# programm-adapter.net
KiCad netlist of a schematic drawn in EAGLE
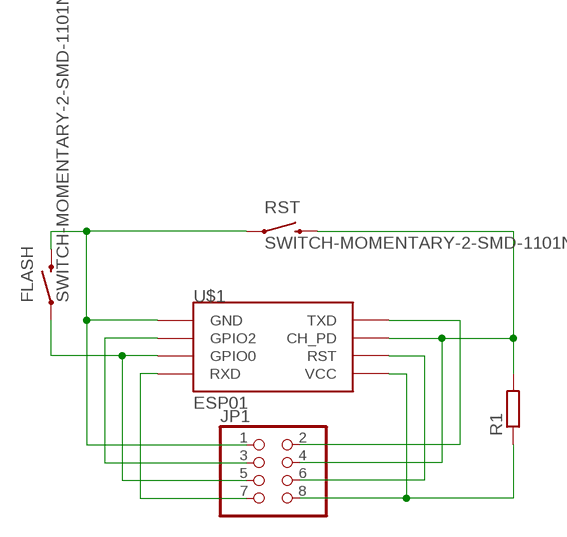
[diagram p0: schematic, sheet 1]

(export (version "E")
  (design (tool "Eeschema 10.0.6"))
  (components
    (comp (ref "FLASH")
      (value "SWITCH-MOMENTARY-2-SMD-1101NE")
      (footprint "eagle-import:TACTILE-SWITCH-1101NE")
      (libsource (lib "eagle-import") (part "SWITCH-MOMENTARY-2-SMD-1101NE"))
    )
    (comp (ref "JP1")
      (value "PINHD-2X4")
      (footprint "eagle-import:2X04")
      (libsource (lib "eagle-import") (part "PINHD-2X4"))
    )
    (comp (ref "R1")
      (value "R-EU_M0805")
      (footprint "eagle-import:M0805")
      (libsource (lib "eagle-import") (part "R-EU_M0805"))
    )
    (comp (ref "RST")
      (value "SWITCH-MOMENTARY-2-SMD-1101NE")
      (footprint "eagle-import:TACTILE-SWITCH-1101NE")
      (libsource (lib "eagle-import") (part "SWITCH-MOMENTARY-2-SMD-1101NE"))
    )
    (comp (ref "U$1")
      (value "ESP01")
      (footprint "eagle-import:ESP01")
      (libsource (lib "eagle-import") (part "ESP01"))
    )
  )
  (nets
    (net (code "1") (name "Net-(FLASH-Pad1)") (class "Default")
      (node (ref "FLASH") (pin "1") (pinfunction "1_1") (pintype "passive"))
      (node (ref "JP1") (pin "5") (pinfunction "5_5") (pintype "passive"))
      (node (ref "U$1") (pin "GPIO0") (pinfunction "GPIO0_GPIO0") (pintype "bidirectional"))
    )
    (net (code "2") (name "Net-(FLASH-Pad2)") (class "Default")
      (node (ref "FLASH") (pin "2") (pinfunction "2_2") (pintype "passive"))
      (node (ref "JP1") (pin "1") (pinfunction "1_1") (pintype "passive"))
      (node (ref "RST") (pin "1") (pinfunction "1_1") (pintype "passive"))
      (node (ref "U$1") (pin "GND") (pinfunction "GND_GND") (pintype "bidirectional"))
    )
    (net (code "3") (name "Net-(JP1-Pad3)") (class "Default")
      (node (ref "JP1") (pin "3") (pinfunction "3_3") (pintype "passive"))
      (node (ref "U$1") (pin "GPIO2") (pinfunction "GPIO2_GPIO2") (pintype "bidirectional"))
    )
    (net (code "4") (name "Net-(JP1-Pad4)") (class "Default")
      (node (ref "JP1") (pin "4") (pinfunction "4_4") (pintype "passive"))
      (node (ref "R1") (pin "2") (pinfunction "2_2") (pintype "passive"))
      (node (ref "RST") (pin "2") (pinfunction "2_2") (pintype "passive"))
      (node (ref "U$1") (pin "CH_PD") (pinfunction "CH_PD_CH_PD") (pintype "bidirectional"))
    )
    (net (code "5") (name "Net-(JP1-Pad6)") (class "Default")
      (node (ref "JP1") (pin "6") (pinfunction "6_6") (pintype "passive"))
      (node (ref "U$1") (pin "RST") (pinfunction "RST_RST") (pintype "bidirectional"))
    )
    (net (code "6") (name "Net-(JP1-Pad8)") (class "Default")
      (node (ref "JP1") (pin "8") (pinfunction "8_8") (pintype "passive"))
      (node (ref "R1") (pin "1") (pinfunction "1_1") (pintype "passive"))
      (node (ref "U$1") (pin "VCC") (pinfunction "VCC_VCC") (pintype "bidirectional"))
    )
    (net (code "7") (name "Net-(U$1-RXD)") (class "Default")
      (node (ref "JP1") (pin "7") (pinfunction "7_7") (pintype "passive"))
      (node (ref "U$1") (pin "RX") (pinfunction "RXD_RX") (pintype "bidirectional"))
    )
    (net (code "8") (name "Net-(U$1-TXD)") (class "Default")
      (node (ref "JP1") (pin "2") (pinfunction "2_2") (pintype "passive"))
      (node (ref "U$1") (pin "TX") (pinfunction "TXD_TX") (pintype "bidirectional"))
    )
  )
)
